# sonoff_relay.net
KiCad netlist of a schematic drawn in EAGLE
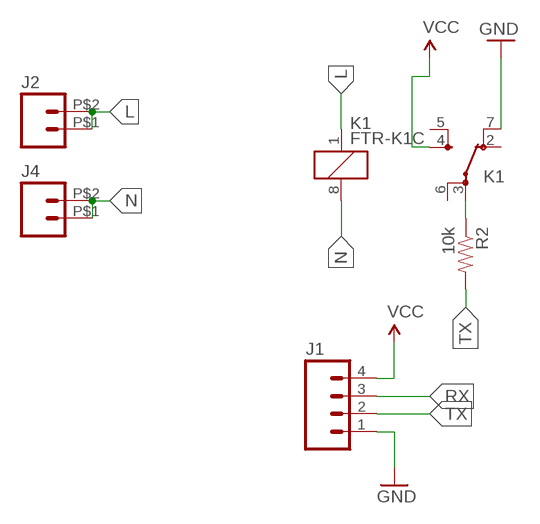
[diagram p0: schematic, sheet 1]

(export (version "E")
  (design (tool "Eeschema 10.0.6"))
  (components
    (comp (ref "J1")
      (value "M04PTH")
      (footprint "eagle-import:1X04")
      (libsource (lib "eagle-import") (part "M04PTH"))
    )
    (comp (ref "J2")
      (value "M02PTH2")
      (footprint "eagle-import:1X02_BIG")
      (libsource (lib "eagle-import") (part "M02PTH2"))
    )
    (comp (ref "J4")
      (value "M02PTH2")
      (footprint "eagle-import:1X02_BIG")
      (libsource (lib "eagle-import") (part "M02PTH2"))
    )
    (comp (ref "K1")
      (value "FTR-K1C")
      (footprint "eagle-import:FTR-K1C")
      (libsource (lib "eagle-import") (part "FTR-K1C"))
    )
    (comp (ref "R2")
      (value "10k")
      (footprint "eagle-import:0805")
      (libsource (lib "eagle-import") (part "RESISTOR0805-RES"))
    )
  )
  (nets
    (net (code "1") (name "GND") (class "Default")
      (node (ref "J1") (pin "1") (pinfunction "1_1") (pintype "passive"))
      (node (ref "K1") (pin "7") (pinfunction "OB_7") (pintype "passive"))
    )
    (net (code "2") (name "L") (class "Default")
      (node (ref "J2") (pin "P$1") (pinfunction "1_P$1") (pintype "passive"))
      (node (ref "J2") (pin "P$2") (pinfunction "2_P$2") (pintype "passive"))
      (node (ref "K1") (pin "1") (pinfunction "1_1") (pintype "passive"))
    )
    (net (code "3") (name "N") (class "Default")
      (node (ref "J4") (pin "P$1") (pinfunction "1_P$1") (pintype "passive"))
      (node (ref "J4") (pin "P$2") (pinfunction "2_P$2") (pintype "passive"))
      (node (ref "K1") (pin "8") (pinfunction "2_8") (pintype "passive"))
    )
    (net (code "4") (name "Net-(K1A-PA)") (class "Default")
      (node (ref "K1") (pin "3") (pinfunction "PA_3") (pintype "passive"))
      (node (ref "R2") (pin "1") (pinfunction "1_1") (pintype "passive"))
    )
    (net (code "5") (name "RX") (class "Default")
      (node (ref "J1") (pin "3") (pinfunction "3_3") (pintype "passive"))
    )
    (net (code "6") (name "TX") (class "Default")
      (node (ref "J1") (pin "2") (pinfunction "2_2") (pintype "passive"))
      (node (ref "R2") (pin "2") (pinfunction "2_2") (pintype "passive"))
    )
    (net (code "7") (name "VCC") (class "Default")
      (node (ref "J1") (pin "4") (pinfunction "4_4") (pintype "passive"))
      (node (ref "K1") (pin "4") (pinfunction "SA_4") (pintype "passive"))
    )
    (net (code "8") (name "unconnected-(K1A-OA-Pad2)") (class "Default")
      (node (ref "K1") (pin "2") (pinfunction "OA_2") (pintype "passive"))
    )
    (net (code "9") (name "unconnected-(K1A-PB-Pad6)") (class "Default")
      (node (ref "K1") (pin "6") (pinfunction "PB_6") (pintype "passive"))
    )
    (net (code "10") (name "unconnected-(K1A-SB-Pad5)") (class "Default")
      (node (ref "K1") (pin "5") (pinfunction "SB_5") (pintype "passive"))
    )
  )
)
